# WL-BPF_L.net
KiCad netlist of a schematic drawn in Altium Designer
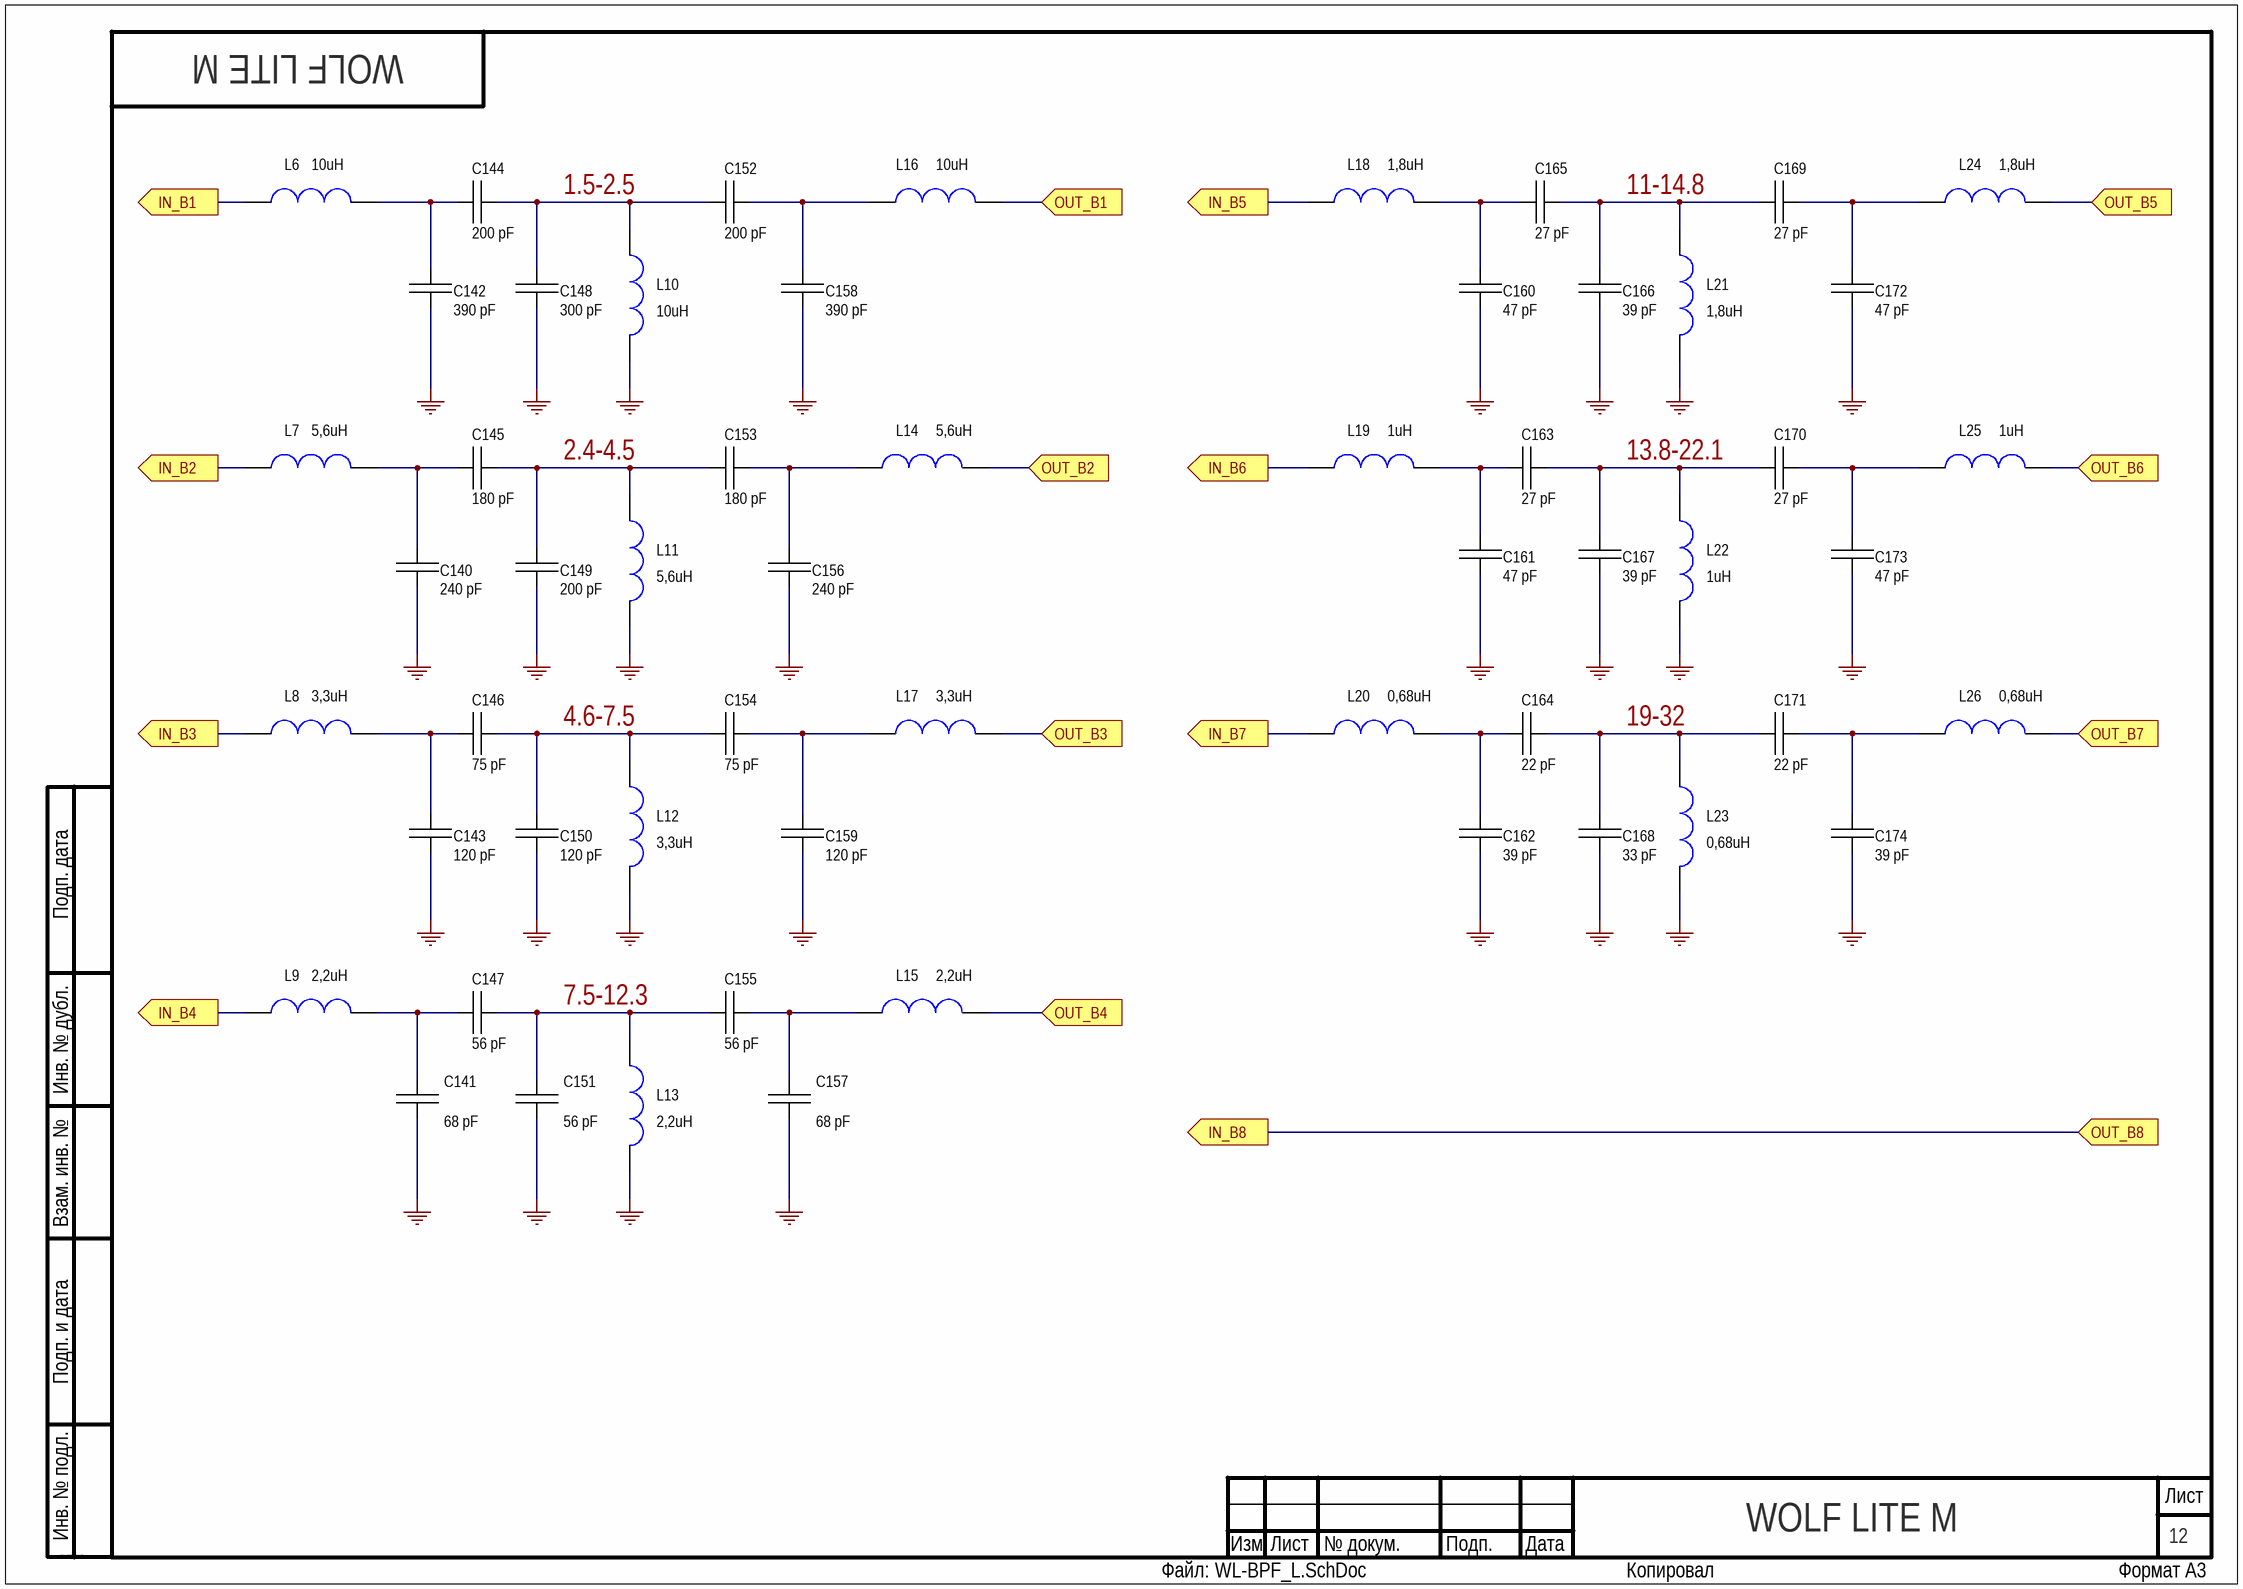
[diagram p0: WL-BPF_L.SchDoc]

(export (version "E")
  (design (tool "Eeschema 10.0.6"))
  (components
    (comp (ref "C140")
      (value "240 pF")
      (footprint "C-0805-0.7")
      (fields
        (field (name "PART NUMBER") "CC0805JRNPO9BN241")
        (field (name "TOLERANCE") "±5%")
        (field (name "VOLTAGE") "50 V")
      )
      (libsource (lib "GOST") (part "Capacitor"))
    )
    (comp (ref "C141")
      (value "68 pF")
      (footprint "C-0805-0.7")
      (fields
        (field (name "PART NUMBER") "CC0805JRNPO9BN680")
        (field (name "TOLERANCE") "±5%")
        (field (name "VOLTAGE") "50 V")
      )
      (libsource (lib "GOST") (part "Capacitor"))
    )
    (comp (ref "C142")
      (value "390 pF")
      (footprint "C-0805-0.7")
      (fields
        (field (name "PART NUMBER") "CC0805JRNPO9BN391")
        (field (name "TOLERANCE") "±5%")
        (field (name "VOLTAGE") "50 V")
      )
      (libsource (lib "GOST") (part "Capacitor"))
    )
    (comp (ref "C143")
      (value "120 pF")
      (footprint "C-0805-0.7")
      (fields
        (field (name "PART NUMBER") "CC0805JRNPO9BN121")
        (field (name "TOLERANCE") "±5%")
        (field (name "VOLTAGE") "50 V")
      )
      (libsource (lib "GOST") (part "Capacitor"))
    )
    (comp (ref "C144")
      (value "200 pF")
      (footprint "C-0805-0.7")
      (fields
        (field (name "PART NUMBER") "CC0805JRNPO9BN201")
        (field (name "TOLERANCE") "±5%")
        (field (name "VOLTAGE") "50 V")
      )
      (libsource (lib "GOST") (part "Capacitor"))
    )
    (comp (ref "C145")
      (value "180 pF")
      (footprint "C-0805-0.7")
      (fields
        (field (name "PART NUMBER") "CC0805JRNPO9BN181")
        (field (name "TOLERANCE") "±5%")
        (field (name "VOLTAGE") "50 V")
      )
      (libsource (lib "GOST") (part "Capacitor"))
    )
    (comp (ref "C146")
      (value "75 pF")
      (footprint "C-0805-0.7")
      (fields
        (field (name "PART NUMBER") "CC0805JRNPO9BN750")
        (field (name "TOLERANCE") "±5%")
        (field (name "VOLTAGE") "50 V")
      )
      (libsource (lib "GOST") (part "Capacitor"))
    )
    (comp (ref "C147")
      (value "56 pF")
      (footprint "C-0805-0.7")
      (fields
        (field (name "PART NUMBER") "CC0805JRNPO9BN560")
        (field (name "TOLERANCE") "±5%")
        (field (name "VOLTAGE") "50 V")
      )
      (libsource (lib "GOST") (part "Capacitor"))
    )
    (comp (ref "C148")
      (value "300 pF")
      (footprint "C-0805-0.7")
      (fields
        (field (name "PART NUMBER") "CC0805JRNPO9BN301")
        (field (name "TOLERANCE") "±5%")
        (field (name "VOLTAGE") "50 V")
      )
      (libsource (lib "GOST") (part "Capacitor"))
    )
    (comp (ref "C149")
      (value "200 pF")
      (footprint "C-0805-0.7")
      (fields
        (field (name "PART NUMBER") "CC0805JRNPO9BN201")
        (field (name "TOLERANCE") "±5%")
        (field (name "VOLTAGE") "50 V")
      )
      (libsource (lib "GOST") (part "Capacitor"))
    )
    (comp (ref "C150")
      (value "120 pF")
      (footprint "C-0805-0.7")
      (fields
        (field (name "PART NUMBER") "CC0805JRNPO9BN121")
        (field (name "TOLERANCE") "±5%")
        (field (name "VOLTAGE") "50 V")
      )
      (libsource (lib "GOST") (part "Capacitor"))
    )
    (comp (ref "C151")
      (value "56 pF")
      (footprint "C-0805-0.7")
      (fields
        (field (name "PART NUMBER") "CC0805JRNPO9BN560")
        (field (name "TOLERANCE") "±5%")
        (field (name "VOLTAGE") "50 V")
      )
      (libsource (lib "GOST") (part "Capacitor"))
    )
    (comp (ref "C152")
      (value "200 pF")
      (footprint "C-0805-0.7")
      (fields
        (field (name "PART NUMBER") "CC0805JRNPO9BN201")
        (field (name "TOLERANCE") "±5%")
        (field (name "VOLTAGE") "50 V")
      )
      (libsource (lib "GOST") (part "Capacitor"))
    )
    (comp (ref "C153")
      (value "180 pF")
      (footprint "C-0805-0.7")
      (fields
        (field (name "PART NUMBER") "CC0805JRNPO9BN181")
        (field (name "TOLERANCE") "±5%")
        (field (name "VOLTAGE") "50 V")
      )
      (libsource (lib "GOST") (part "Capacitor"))
    )
    (comp (ref "C154")
      (value "75 pF")
      (footprint "C-0805-0.7")
      (fields
        (field (name "PART NUMBER") "CC0805JRNPO9BN750")
        (field (name "TOLERANCE") "±5%")
        (field (name "VOLTAGE") "50 V")
      )
      (libsource (lib "GOST") (part "Capacitor"))
    )
    (comp (ref "C155")
      (value "56 pF")
      (footprint "C-0805-0.7")
      (fields
        (field (name "PART NUMBER") "CC0805JRNPO9BN560")
        (field (name "TOLERANCE") "±5%")
        (field (name "VOLTAGE") "50 V")
      )
      (libsource (lib "GOST") (part "Capacitor"))
    )
    (comp (ref "C156")
      (value "240 pF")
      (footprint "C-0805-0.7")
      (fields
        (field (name "PART NUMBER") "CC0805JRNPO9BN241")
        (field (name "TOLERANCE") "±5%")
        (field (name "VOLTAGE") "50 V")
      )
      (libsource (lib "GOST") (part "Capacitor"))
    )
    (comp (ref "C157")
      (value "68 pF")
      (footprint "C-0805-0.7")
      (fields
        (field (name "PART NUMBER") "CC0805JRNPO9BN680")
        (field (name "TOLERANCE") "±5%")
        (field (name "VOLTAGE") "50 V")
      )
      (libsource (lib "GOST") (part "Capacitor"))
    )
    (comp (ref "C158")
      (value "390 pF")
      (footprint "C-0805-0.7")
      (fields
        (field (name "PART NUMBER") "CC0805JRNPO9BN391")
        (field (name "TOLERANCE") "±5%")
        (field (name "VOLTAGE") "50 V")
      )
      (libsource (lib "GOST") (part "Capacitor"))
    )
    (comp (ref "C159")
      (value "120 pF")
      (footprint "C-0805-0.7")
      (fields
        (field (name "PART NUMBER") "CC0805JRNPO9BN121")
        (field (name "TOLERANCE") "±5%")
        (field (name "VOLTAGE") "50 V")
      )
      (libsource (lib "GOST") (part "Capacitor"))
    )
    (comp (ref "C160")
      (value "47 pF")
      (footprint "C-0805-0.7")
      (fields
        (field (name "PART NUMBER") "CC0805JRNPO9BN470")
        (field (name "TOLERANCE") "±5%")
        (field (name "VOLTAGE") "50 V")
      )
      (libsource (lib "GOST") (part "Capacitor"))
    )
    (comp (ref "C161")
      (value "47 pF")
      (footprint "C-0805-0.7")
      (fields
        (field (name "PART NUMBER") "CC0805JRNPO9BN470")
        (field (name "TOLERANCE") "±5%")
        (field (name "VOLTAGE") "50 V")
      )
      (libsource (lib "GOST") (part "Capacitor"))
    )
    (comp (ref "C162")
      (value "39 pF")
      (footprint "C-0805-0.7")
      (fields
        (field (name "PART NUMBER") "CC0805JRNPO9BN390")
        (field (name "TOLERANCE") "±5%")
        (field (name "VOLTAGE") "50 V")
      )
      (libsource (lib "GOST") (part "Capacitor"))
    )
    (comp (ref "C163")
      (value "27 pF")
      (footprint "C-0805-0.7")
      (fields
        (field (name "PART NUMBER") "CC0805JRNPO9BN270")
        (field (name "TOLERANCE") "±5%")
        (field (name "VOLTAGE") "50 V")
      )
      (libsource (lib "GOST") (part "Capacitor"))
    )
    (comp (ref "C164")
      (value "22 pF")
      (footprint "C-0805-0.7")
      (fields
        (field (name "PART NUMBER") "CC0805JRNPO9BN220")
        (field (name "TOLERANCE") "±5%")
        (field (name "VOLTAGE") "50 V")
      )
      (libsource (lib "GOST") (part "Capacitor"))
    )
    (comp (ref "C165")
      (value "27 pF")
      (footprint "C-0805-0.7")
      (fields
        (field (name "PART NUMBER") "CC0805JRNPO9BN270")
        (field (name "TOLERANCE") "±5%")
        (field (name "VOLTAGE") "50 V")
      )
      (libsource (lib "GOST") (part "Capacitor"))
    )
    (comp (ref "C166")
      (value "39 pF")
      (footprint "C-0805-0.7")
      (fields
        (field (name "PART NUMBER") "CC0805JRNPO9BN390")
        (field (name "TOLERANCE") "±5%")
        (field (name "VOLTAGE") "50 V")
      )
      (libsource (lib "GOST") (part "Capacitor"))
    )
    (comp (ref "C167")
      (value "39 pF")
      (footprint "C-0805-0.7")
      (fields
        (field (name "PART NUMBER") "CC0805JRNPO9BN390")
        (field (name "TOLERANCE") "±5%")
        (field (name "VOLTAGE") "50 V")
      )
      (libsource (lib "GOST") (part "Capacitor"))
    )
    (comp (ref "C168")
      (value "33 pF")
      (footprint "C-0805-0.7")
      (fields
        (field (name "PART NUMBER") "CC0805JRNPO9BN330")
        (field (name "TOLERANCE") "±5%")
        (field (name "VOLTAGE") "50 V")
      )
      (libsource (lib "GOST") (part "Capacitor"))
    )
    (comp (ref "C169")
      (value "27 pF")
      (footprint "C-0805-0.7")
      (fields
        (field (name "PART NUMBER") "CC0805JRNPO9BN270")
        (field (name "TOLERANCE") "±5%")
        (field (name "VOLTAGE") "50 V")
      )
      (libsource (lib "GOST") (part "Capacitor"))
    )
    (comp (ref "C170")
      (value "27 pF")
      (footprint "C-0805-0.7")
      (fields
        (field (name "PART NUMBER") "CC0805JRNPO9BN270")
        (field (name "TOLERANCE") "±5%")
        (field (name "VOLTAGE") "50 V")
      )
      (libsource (lib "GOST") (part "Capacitor"))
    )
    (comp (ref "C171")
      (value "22 pF")
      (footprint "C-0805-0.7")
      (fields
        (field (name "PART NUMBER") "CC0805JRNPO9BN220")
        (field (name "TOLERANCE") "±5%")
        (field (name "VOLTAGE") "50 V")
      )
      (libsource (lib "GOST") (part "Capacitor"))
    )
    (comp (ref "C172")
      (value "47 pF")
      (footprint "C-0805-0.7")
      (fields
        (field (name "PART NUMBER") "CC0805JRNPO9BN470")
        (field (name "TOLERANCE") "±5%")
        (field (name "VOLTAGE") "50 V")
      )
      (libsource (lib "GOST") (part "Capacitor"))
    )
    (comp (ref "C173")
      (value "47 pF")
      (footprint "C-0805-0.7")
      (fields
        (field (name "PART NUMBER") "CC0805JRNPO9BN470")
        (field (name "TOLERANCE") "±5%")
        (field (name "VOLTAGE") "50 V")
      )
      (libsource (lib "GOST") (part "Capacitor"))
    )
    (comp (ref "C174")
      (value "39 pF")
      (footprint "C-0805-0.7")
      (fields
        (field (name "PART NUMBER") "CC0805JRNPO9BN390")
        (field (name "TOLERANCE") "±5%")
        (field (name "VOLTAGE") "50 V")
      )
      (libsource (lib "GOST") (part "Capacitor"))
    )
    (comp (ref "L6")
      (value "10uH")
      (footprint "L-1210")
      (fields
        (field (name "PART NUMBER") "FHW1210IF100JST")
        (field (name "MANUFACTURER") "FH(Guangdong Fenghua Advanced Tech)")
      )
      (libsource (lib "GOST") (part "Inductor"))
    )
    (comp (ref "L7")
      (value "5,6uH")
      (footprint "L-1210")
      (fields
        (field (name "PART NUMBER") "FHW1210IF5R6JST")
        (field (name "MANUFACTURER") "FH(Guangdong Fenghua Advanced Tech)")
      )
      (libsource (lib "GOST") (part "Inductor"))
    )
    (comp (ref "L8")
      (value "3,3uH")
      (footprint "L-1210")
      (fields
        (field (name "PART NUMBER") "FHW1210IF3R3JST")
        (field (name "MANUFACTURER") "FH(Guangdong Fenghua Advanced Tech)")
      )
      (libsource (lib "GOST") (part "Inductor"))
    )
    (comp (ref "L9")
      (value "2,2uH")
      (footprint "L-1210")
      (fields
        (field (name "PART NUMBER") "FHW1210IF2R2JST")
        (field (name "MANUFACTURER") "FH(Guangdong Fenghua Advanced Tech)")
      )
      (libsource (lib "GOST") (part "Inductor"))
    )
    (comp (ref "L10")
      (value "10uH")
      (footprint "L-1210")
      (fields
        (field (name "PART NUMBER") "FHW1210IF100JST")
        (field (name "MANUFACTURER") "FH(Guangdong Fenghua Advanced Tech)")
      )
      (libsource (lib "GOST") (part "Inductor"))
    )
    (comp (ref "L11")
      (value "5,6uH")
      (footprint "L-1210")
      (fields
        (field (name "PART NUMBER") "FHW1210IF5R6JST")
        (field (name "MANUFACTURER") "FH(Guangdong Fenghua Advanced Tech)")
      )
      (libsource (lib "GOST") (part "Inductor"))
    )
    (comp (ref "L12")
      (value "3,3uH")
      (footprint "L-1210")
      (fields
        (field (name "PART NUMBER") "FHW1210IF3R3JST")
        (field (name "MANUFACTURER") "FH(Guangdong Fenghua Advanced Tech)")
      )
      (libsource (lib "GOST") (part "Inductor"))
    )
    (comp (ref "L13")
      (value "2,2uH")
      (footprint "L-1210")
      (fields
        (field (name "PART NUMBER") "FHW1210IF2R2JST")
        (field (name "MANUFACTURER") "FH(Guangdong Fenghua Advanced Tech)")
      )
      (libsource (lib "GOST") (part "Inductor"))
    )
    (comp (ref "L14")
      (value "5,6uH")
      (footprint "L-1210")
      (fields
        (field (name "PART NUMBER") "FHW1210IF5R6JST")
        (field (name "MANUFACTURER") "FH(Guangdong Fenghua Advanced Tech)")
      )
      (libsource (lib "GOST") (part "Inductor"))
    )
    (comp (ref "L15")
      (value "2,2uH")
      (footprint "L-1210")
      (fields
        (field (name "PART NUMBER") "FHW1210IF2R2JST")
        (field (name "MANUFACTURER") "FH(Guangdong Fenghua Advanced Tech)")
      )
      (libsource (lib "GOST") (part "Inductor"))
    )
    (comp (ref "L16")
      (value "10uH")
      (footprint "L-1210")
      (fields
        (field (name "PART NUMBER") "FHW1210IF100JST")
        (field (name "MANUFACTURER") "FH(Guangdong Fenghua Advanced Tech)")
      )
      (libsource (lib "GOST") (part "Inductor"))
    )
    (comp (ref "L17")
      (value "3,3uH")
      (footprint "L-1210")
      (fields
        (field (name "PART NUMBER") "FHW1210IF3R3JST")
        (field (name "MANUFACTURER") "FH(Guangdong Fenghua Advanced Tech)")
      )
      (libsource (lib "GOST") (part "Inductor"))
    )
    (comp (ref "L18")
      (value "1,8uH")
      (footprint "L-1210")
      (fields
        (field (name "PART NUMBER") "FHW1210IF1R8JST")
        (field (name "MANUFACTURER") "FH(Guangdong Fenghua Advanced Tech)")
      )
      (libsource (lib "GOST") (part "Inductor"))
    )
    (comp (ref "L19")
      (value "1uH")
      (footprint "L-1210")
      (fields
        (field (name "PART NUMBER") "FHW1210IF1R0KST")
        (field (name "MANUFACTURER") "FH(Guangdong Fenghua Advanced Tech)")
      )
      (libsource (lib "GOST") (part "Inductor"))
    )
    (comp (ref "L20")
      (value "0,68uH")
      (footprint "L-1210")
      (fields
        (field (name "PART NUMBER") "FHW1210HCR68JGT")
        (field (name "MANUFACTURER") "FH(Guangdong Fenghua Advanced Tech)")
      )
      (libsource (lib "GOST") (part "Inductor"))
    )
    (comp (ref "L21")
      (value "1,8uH")
      (footprint "L-1210")
      (fields
        (field (name "PART NUMBER") "FHW1210IF1R8JST")
        (field (name "MANUFACTURER") "FH(Guangdong Fenghua Advanced Tech)")
      )
      (libsource (lib "GOST") (part "Inductor"))
    )
    (comp (ref "L22")
      (value "1uH")
      (footprint "L-1210")
      (fields
        (field (name "PART NUMBER") "FHW1210IF1R0KST")
        (field (name "MANUFACTURER") "FH(Guangdong Fenghua Advanced Tech)")
      )
      (libsource (lib "GOST") (part "Inductor"))
    )
    (comp (ref "L23")
      (value "0,68uH")
      (footprint "L-1210")
      (fields
        (field (name "PART NUMBER") "FHW1210HCR68JGT")
        (field (name "MANUFACTURER") "FH(Guangdong Fenghua Advanced Tech)")
      )
      (libsource (lib "GOST") (part "Inductor"))
    )
    (comp (ref "L24")
      (value "1,8uH")
      (footprint "L-1210")
      (fields
        (field (name "PART NUMBER") "FHW1210IF1R8JST")
        (field (name "MANUFACTURER") "FH(Guangdong Fenghua Advanced Tech)")
      )
      (libsource (lib "GOST") (part "Inductor"))
    )
    (comp (ref "L25")
      (value "1uH")
      (footprint "L-1210")
      (fields
        (field (name "PART NUMBER") "FHW1210IF1R0KST")
        (field (name "MANUFACTURER") "FH(Guangdong Fenghua Advanced Tech)")
      )
      (libsource (lib "GOST") (part "Inductor"))
    )
    (comp (ref "L26")
      (value "0,68uH")
      (footprint "L-1210")
      (fields
        (field (name "PART NUMBER") "FHW1210HCR68JGT")
        (field (name "MANUFACTURER") "FH(Guangdong Fenghua Advanced Tech)")
      )
      (libsource (lib "GOST") (part "Inductor"))
    )
  )
  (nets
    (net (code "1") (name "/IN_B1") (class "Default")
      (node (ref "L6") (pin "1") (pinfunction "1_1") (pintype "passive"))
    )
    (net (code "2") (name "/IN_B2") (class "Default")
      (node (ref "L7") (pin "1") (pinfunction "1_1") (pintype "passive"))
    )
    (net (code "3") (name "/IN_B3") (class "Default")
      (node (ref "L8") (pin "1") (pinfunction "1_1") (pintype "passive"))
    )
    (net (code "4") (name "/IN_B4") (class "Default")
      (node (ref "L9") (pin "1") (pinfunction "1_1") (pintype "passive"))
    )
    (net (code "5") (name "/IN_B5") (class "Default")
      (node (ref "L18") (pin "1") (pinfunction "1_1") (pintype "passive"))
    )
    (net (code "6") (name "/IN_B6") (class "Default")
      (node (ref "L19") (pin "1") (pinfunction "1_1") (pintype "passive"))
    )
    (net (code "7") (name "/IN_B7") (class "Default")
      (node (ref "L20") (pin "1") (pinfunction "1_1") (pintype "passive"))
    )
    (net (code "9") (name "/OUT_B1") (class "Default")
      (node (ref "L16") (pin "2") (pinfunction "2_2") (pintype "passive"))
    )
    (net (code "10") (name "/OUT_B2") (class "Default")
      (node (ref "L14") (pin "2") (pinfunction "2_2") (pintype "passive"))
    )
    (net (code "11") (name "/OUT_B3") (class "Default")
      (node (ref "L17") (pin "2") (pinfunction "2_2") (pintype "passive"))
    )
    (net (code "12") (name "/OUT_B4") (class "Default")
      (node (ref "L15") (pin "2") (pinfunction "2_2") (pintype "passive"))
    )
    (net (code "13") (name "/OUT_B5") (class "Default")
      (node (ref "L24") (pin "2") (pinfunction "2_2") (pintype "passive"))
    )
    (net (code "14") (name "/OUT_B6") (class "Default")
      (node (ref "L25") (pin "2") (pinfunction "2_2") (pintype "passive"))
    )
    (net (code "15") (name "/OUT_B7") (class "Default")
      (node (ref "L26") (pin "2") (pinfunction "2_2") (pintype "passive"))
    )
    (net (code "16") (name "GND") (class "Default")
      (node (ref "C140") (pin "1") (pinfunction "1_1") (pintype "passive"))
      (node (ref "C141") (pin "1") (pinfunction "1_1") (pintype "passive"))
      (node (ref "C142") (pin "1") (pinfunction "1_1") (pintype "passive"))
      (node (ref "C143") (pin "1") (pinfunction "1_1") (pintype "passive"))
      (node (ref "C148") (pin "1") (pinfunction "1_1") (pintype "passive"))
      (node (ref "C149") (pin "1") (pinfunction "1_1") (pintype "passive"))
      (node (ref "C150") (pin "1") (pinfunction "1_1") (pintype "passive"))
      (node (ref "C151") (pin "1") (pinfunction "1_1") (pintype "passive"))
      (node (ref "C156") (pin "1") (pinfunction "1_1") (pintype "passive"))
      (node (ref "C157") (pin "1") (pinfunction "1_1") (pintype "passive"))
      (node (ref "C158") (pin "1") (pinfunction "1_1") (pintype "passive"))
      (node (ref "C159") (pin "1") (pinfunction "1_1") (pintype "passive"))
      (node (ref "C160") (pin "1") (pinfunction "1_1") (pintype "passive"))
      (node (ref "C161") (pin "1") (pinfunction "1_1") (pintype "passive"))
      (node (ref "C162") (pin "1") (pinfunction "1_1") (pintype "passive"))
      (node (ref "C166") (pin "1") (pinfunction "1_1") (pintype "passive"))
      (node (ref "C167") (pin "1") (pinfunction "1_1") (pintype "passive"))
      (node (ref "C168") (pin "1") (pinfunction "1_1") (pintype "passive"))
      (node (ref "C172") (pin "1") (pinfunction "1_1") (pintype "passive"))
      (node (ref "C173") (pin "1") (pinfunction "1_1") (pintype "passive"))
      (node (ref "C174") (pin "1") (pinfunction "1_1") (pintype "passive"))
      (node (ref "L10") (pin "2") (pinfunction "2_2") (pintype "passive"))
      (node (ref "L11") (pin "2") (pinfunction "2_2") (pintype "passive"))
      (node (ref "L12") (pin "2") (pinfunction "2_2") (pintype "passive"))
      (node (ref "L13") (pin "2") (pinfunction "2_2") (pintype "passive"))
      (node (ref "L21") (pin "2") (pinfunction "2_2") (pintype "passive"))
      (node (ref "L22") (pin "2") (pinfunction "2_2") (pintype "passive"))
      (node (ref "L23") (pin "2") (pinfunction "2_2") (pintype "passive"))
    )
    (net (code "17") (name "Net-(C140-Pad2)") (class "Default")
      (node (ref "C140") (pin "2") (pinfunction "2_2") (pintype "passive"))
      (node (ref "C145") (pin "1") (pinfunction "1_1") (pintype "passive"))
      (node (ref "L7") (pin "2") (pinfunction "2_2") (pintype "passive"))
    )
    (net (code "18") (name "Net-(C141-Pad2)") (class "Default")
      (node (ref "C141") (pin "2") (pinfunction "2_2") (pintype "passive"))
      (node (ref "C147") (pin "2") (pinfunction "2_2") (pintype "passive"))
      (node (ref "L9") (pin "2") (pinfunction "2_2") (pintype "passive"))
    )
    (net (code "19") (name "Net-(C142-Pad2)") (class "Default")
      (node (ref "C142") (pin "2") (pinfunction "2_2") (pintype "passive"))
      (node (ref "C144") (pin "1") (pinfunction "1_1") (pintype "passive"))
      (node (ref "L6") (pin "2") (pinfunction "2_2") (pintype "passive"))
    )
    (net (code "20") (name "Net-(C143-Pad2)") (class "Default")
      (node (ref "C143") (pin "2") (pinfunction "2_2") (pintype "passive"))
      (node (ref "C146") (pin "1") (pinfunction "1_1") (pintype "passive"))
      (node (ref "L8") (pin "2") (pinfunction "2_2") (pintype "passive"))
    )
    (net (code "21") (name "Net-(C144-Pad2)") (class "Default")
      (node (ref "C144") (pin "2") (pinfunction "2_2") (pintype "passive"))
      (node (ref "C148") (pin "2") (pinfunction "2_2") (pintype "passive"))
      (node (ref "C152") (pin "1") (pinfunction "1_1") (pintype "passive"))
      (node (ref "L10") (pin "1") (pinfunction "1_1") (pintype "passive"))
    )
    (net (code "22") (name "Net-(C145-Pad2)") (class "Default")
      (node (ref "C145") (pin "2") (pinfunction "2_2") (pintype "passive"))
      (node (ref "C149") (pin "2") (pinfunction "2_2") (pintype "passive"))
      (node (ref "C153") (pin "1") (pinfunction "1_1") (pintype "passive"))
      (node (ref "L11") (pin "1") (pinfunction "1_1") (pintype "passive"))
    )
    (net (code "23") (name "Net-(C146-Pad2)") (class "Default")
      (node (ref "C146") (pin "2") (pinfunction "2_2") (pintype "passive"))
      (node (ref "C150") (pin "2") (pinfunction "2_2") (pintype "passive"))
      (node (ref "C154") (pin "1") (pinfunction "1_1") (pintype "passive"))
      (node (ref "L12") (pin "1") (pinfunction "1_1") (pintype "passive"))
    )
    (net (code "24") (name "Net-(C147-Pad1)") (class "Default")
      (node (ref "C147") (pin "1") (pinfunction "1_1") (pintype "passive"))
      (node (ref "C151") (pin "2") (pinfunction "2_2") (pintype "passive"))
      (node (ref "C155") (pin "2") (pinfunction "2_2") (pintype "passive"))
      (node (ref "L13") (pin "1") (pinfunction "1_1") (pintype "passive"))
    )
    (net (code "25") (name "Net-(C152-Pad2)") (class "Default")
      (node (ref "C152") (pin "2") (pinfunction "2_2") (pintype "passive"))
      (node (ref "C158") (pin "2") (pinfunction "2_2") (pintype "passive"))
      (node (ref "L16") (pin "1") (pinfunction "1_1") (pintype "passive"))
    )
    (net (code "26") (name "Net-(C153-Pad2)") (class "Default")
      (node (ref "C153") (pin "2") (pinfunction "2_2") (pintype "passive"))
      (node (ref "C156") (pin "2") (pinfunction "2_2") (pintype "passive"))
      (node (ref "L14") (pin "1") (pinfunction "1_1") (pintype "passive"))
    )
    (net (code "27") (name "Net-(C154-Pad2)") (class "Default")
      (node (ref "C154") (pin "2") (pinfunction "2_2") (pintype "passive"))
      (node (ref "C159") (pin "2") (pinfunction "2_2") (pintype "passive"))
      (node (ref "L17") (pin "1") (pinfunction "1_1") (pintype "passive"))
    )
    (net (code "28") (name "Net-(C155-Pad1)") (class "Default")
      (node (ref "C155") (pin "1") (pinfunction "1_1") (pintype "passive"))
      (node (ref "C157") (pin "2") (pinfunction "2_2") (pintype "passive"))
      (node (ref "L15") (pin "1") (pinfunction "1_1") (pintype "passive"))
    )
    (net (code "29") (name "Net-(C160-Pad2)") (class "Default")
      (node (ref "C160") (pin "2") (pinfunction "2_2") (pintype "passive"))
      (node (ref "C165") (pin "1") (pinfunction "1_1") (pintype "passive"))
      (node (ref "L18") (pin "2") (pinfunction "2_2") (pintype "passive"))
    )
    (net (code "30") (name "Net-(C161-Pad2)") (class "Default")
      (node (ref "C161") (pin "2") (pinfunction "2_2") (pintype "passive"))
      (node (ref "C163") (pin "1") (pinfunction "1_1") (pintype "passive"))
      (node (ref "L19") (pin "2") (pinfunction "2_2") (pintype "passive"))
    )
    (net (code "31") (name "Net-(C162-Pad2)") (class "Default")
      (node (ref "C162") (pin "2") (pinfunction "2_2") (pintype "passive"))
      (node (ref "C164") (pin "1") (pinfunction "1_1") (pintype "passive"))
      (node (ref "L20") (pin "2") (pinfunction "2_2") (pintype "passive"))
    )
    (net (code "32") (name "Net-(C163-Pad2)") (class "Default")
      (node (ref "C163") (pin "2") (pinfunction "2_2") (pintype "passive"))
      (node (ref "C167") (pin "2") (pinfunction "2_2") (pintype "passive"))
      (node (ref "C170") (pin "1") (pinfunction "1_1") (pintype "passive"))
      (node (ref "L22") (pin "1") (pinfunction "1_1") (pintype "passive"))
    )
    (net (code "33") (name "Net-(C164-Pad2)") (class "Default")
      (node (ref "C164") (pin "2") (pinfunction "2_2") (pintype "passive"))
      (node (ref "C168") (pin "2") (pinfunction "2_2") (pintype "passive"))
      (node (ref "C171") (pin "1") (pinfunction "1_1") (pintype "passive"))
      (node (ref "L23") (pin "1") (pinfunction "1_1") (pintype "passive"))
    )
    (net (code "34") (name "Net-(C165-Pad2)") (class "Default")
      (node (ref "C165") (pin "2") (pinfunction "2_2") (pintype "passive"))
      (node (ref "C166") (pin "2") (pinfunction "2_2") (pintype "passive"))
      (node (ref "C169") (pin "1") (pinfunction "1_1") (pintype "passive"))
      (node (ref "L21") (pin "1") (pinfunction "1_1") (pintype "passive"))
    )
    (net (code "35") (name "Net-(C169-Pad2)") (class "Default")
      (node (ref "C169") (pin "2") (pinfunction "2_2") (pintype "passive"))
      (node (ref "C172") (pin "2") (pinfunction "2_2") (pintype "passive"))
      (node (ref "L24") (pin "1") (pinfunction "1_1") (pintype "passive"))
    )
    (net (code "36") (name "Net-(C170-Pad2)") (class "Default")
      (node (ref "C170") (pin "2") (pinfunction "2_2") (pintype "passive"))
      (node (ref "C173") (pin "2") (pinfunction "2_2") (pintype "passive"))
      (node (ref "L25") (pin "1") (pinfunction "1_1") (pintype "passive"))
    )
    (net (code "37") (name "Net-(C171-Pad2)") (class "Default")
      (node (ref "C171") (pin "2") (pinfunction "2_2") (pintype "passive"))
      (node (ref "C174") (pin "2") (pinfunction "2_2") (pintype "passive"))
      (node (ref "L26") (pin "1") (pinfunction "1_1") (pintype "passive"))
    )
  )
)
